# SoftCore_SA_P2_PG7.net
KiCad netlist of a schematic drawn in Altium Designer
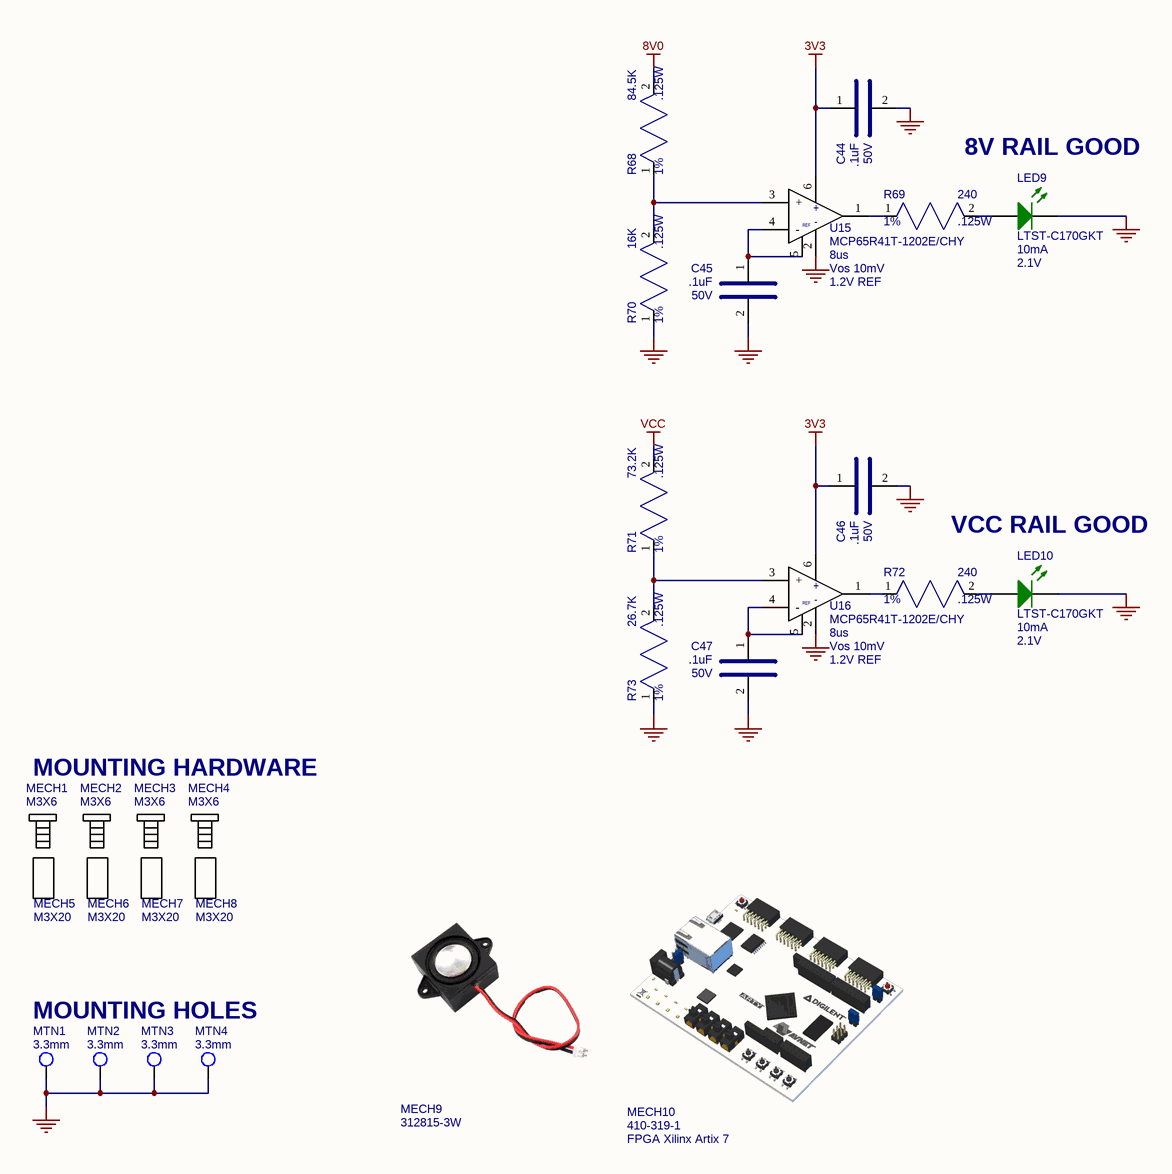
[diagram p0: SoftCore_SA_P2_PG7.SchDoc]

(export (version "E")
  (design (tool "Eeschema 10.0.6"))
  (components
    (comp (ref "C44")
      (value ".1uF")
      (footprint "CAP_0805")
      (description "CAP CER 0.1UF 50V X7R 0805")
      (fields
        (field (name "MFG") "KYOCERA AVX")
        (field (name "VOLTAGE") "50V")
        (field (name "Comment") "KGM21NR71H104KT")
      )
      (libsource (lib "IMR_LIB_SCH_R2") (part "CAP_SMD_0.1UF_50V_0805"))
    )
    (comp (ref "C45")
      (value ".1uF")
      (footprint "CAP_0805")
      (description "CAP CER 0.1UF 50V X7R 0805")
      (fields
        (field (name "MFG") "KYOCERA AVX")
        (field (name "VOLTAGE") "50V")
        (field (name "Comment") "KGM21NR71H104KT")
      )
      (libsource (lib "IMR_LIB_SCH_R2") (part "CAP_SMD_0.1UF_50V_0805"))
    )
    (comp (ref "C46")
      (value ".1uF")
      (footprint "CAP_0805")
      (description "CAP CER 0.1UF 50V X7R 0805")
      (fields
        (field (name "MFG") "KYOCERA AVX")
        (field (name "VOLTAGE") "50V")
        (field (name "Comment") "KGM21NR71H104KT")
      )
      (libsource (lib "IMR_LIB_SCH_R2") (part "CAP_SMD_0.1UF_50V_0805"))
    )
    (comp (ref "C47")
      (value ".1uF")
      (footprint "CAP_0805")
      (description "CAP CER 0.1UF 50V X7R 0805")
      (fields
        (field (name "MFG") "KYOCERA AVX")
        (field (name "VOLTAGE") "50V")
        (field (name "Comment") "KGM21NR71H104KT")
      )
      (libsource (lib "IMR_LIB_SCH_R2") (part "CAP_SMD_0.1UF_50V_0805"))
    )
    (comp (ref "LED9")
      (value "2.1V")
      (footprint "LED_0805")
      (description "LED GREEN CLEAR SMD")
      (fields
        (field (name "MFG") "Lite-On")
        (field (name "MFG_PN") "LTST-C170GKT")
        (field (name "CURRENT") "10mA")
        (field (name "Comment") "LTST-C170GKT")
      )
      (libsource (lib "IMR_LIB_SCH_R2") (part "LED_GREEN_LTST-C170GKT"))
    )
    (comp (ref "LED10")
      (value "2.1V")
      (footprint "LED_0805")
      (description "LED GREEN CLEAR SMD")
      (fields
        (field (name "MFG") "Lite-On")
        (field (name "MFG_PN") "LTST-C170GKT")
        (field (name "CURRENT") "10mA")
        (field (name "Comment") "LTST-C170GKT")
      )
      (libsource (lib "IMR_LIB_SCH_R2") (part "LED_GREEN_LTST-C170GKT"))
    )
    (comp (ref "MECH1")
      (value "RM3X6MM 2701")
      (footprint "MECHANICAL_SCREW_M3X6")
      (description "SCREW M3X6 PAN HEAD SS")
      (fields (field (name "MFG") "APM Hexseal") (field (name "SIZE") "M3X6"))
      (libsource (lib "IMR_LIB_SCH_R2") (part "MECHANICAL_SCREW_M3X6_PAN_HEAD"))
    )
    (comp (ref "MECH2")
      (value "RM3X6MM 2701")
      (footprint "MECHANICAL_SCREW_M3X6")
      (description "SCREW M3X6 PAN HEAD SS")
      (fields (field (name "MFG") "APM Hexseal") (field (name "SIZE") "M3X6"))
      (libsource (lib "IMR_LIB_SCH_R2") (part "MECHANICAL_SCREW_M3X6_PAN_HEAD"))
    )
    (comp (ref "MECH3")
      (value "RM3X6MM 2701")
      (footprint "MECHANICAL_SCREW_M3X6")
      (description "SCREW M3X6 PAN HEAD SS")
      (fields (field (name "MFG") "APM Hexseal") (field (name "SIZE") "M3X6"))
      (libsource (lib "IMR_LIB_SCH_R2") (part "MECHANICAL_SCREW_M3X6_PAN_HEAD"))
    )
    (comp (ref "MECH4")
      (value "RM3X6MM 2701")
      (footprint "MECHANICAL_SCREW_M3X6")
      (description "SCREW M3X6 PAN HEAD SS")
      (fields (field (name "MFG") "APM Hexseal") (field (name "SIZE") "M3X6"))
      (libsource (lib "IMR_LIB_SCH_R2") (part "MECHANICAL_SCREW_M3X6_PAN_HEAD"))
    )
    (comp (ref "MECH5")
      (value "24407")
      (footprint "MECHANICAL_SPACER_F_F_M3X20")
      (description "HEX STANDOFF M3 BRASS 20MM")
      (fields (field (name "MFG") "Keystone Electronics") (field (name "SIZE") "M3X20"))
      (libsource (lib "IMR_LIB_SCH_R2") (part "MECHANICAL_STANDOFF_M3X20"))
    )
    (comp (ref "MECH6")
      (value "24407")
      (footprint "MECHANICAL_SPACER_F_F_M3X20")
      (description "HEX STANDOFF M3 BRASS 20MM")
      (fields (field (name "MFG") "Keystone Electronics") (field (name "SIZE") "M3X20"))
      (libsource (lib "IMR_LIB_SCH_R2") (part "MECHANICAL_STANDOFF_M3X20"))
    )
    (comp (ref "MECH7")
      (value "24407")
      (footprint "MECHANICAL_SPACER_F_F_M3X20")
      (description "HEX STANDOFF M3 BRASS 20MM")
      (fields (field (name "MFG") "Keystone Electronics") (field (name "SIZE") "M3X20"))
      (libsource (lib "IMR_LIB_SCH_R2") (part "MECHANICAL_STANDOFF_M3X20"))
    )
    (comp (ref "MECH8")
      (value "24407")
      (footprint "MECHANICAL_SPACER_F_F_M3X20")
      (description "HEX STANDOFF M3 BRASS 20MM")
      (fields (field (name "MFG") "Keystone Electronics") (field (name "SIZE") "M3X20"))
      (libsource (lib "IMR_LIB_SCH_R2") (part "MECHANICAL_STANDOFF_M3X20"))
    )
    (comp (ref "MECH9")
      (value "312815-3W")
      (footprint "312815-3W_PCB")
      (description "SPEAKER PANEL MOUNT")
      (fields (field (name "MFG") "ARDUINO") (field (name "MFG_PN") "312815-3W"))
      (libsource (lib "IMR_LIB_SCH_R2") (part "MECHANICAL_SPEAKER_MOUNTED"))
    )
    (comp (ref "MECH10")
      (value "FPGA Xilinx Artix 7")
      (footprint "ARTY_A7_DEV_BOARD")
      (description "DEVELOPMENT BOARD FPGA XILINX A7")
      (fields
        (field (name "MFG") "Digilent, Inc.")
        (field (name "MFG_PN") "410-319-1")
        (field (name "Comment") "410-319-1")
      )
      (libsource (lib "IMR_LIB_SCH_R2") (part "MODULE_ARTY_A7"))
    )
    (comp (ref "MTN1")
      (value "~")
      (footprint "PMG_MT_HOLE_3.3MM")
      (description "MOUNTING HOLE 3.3MM")
      (fields (field (name "HOLE SIZE") "3.3mm"))
      (libsource (lib "IMR_LIB_SCH_R2") (part "MTN_HOLE_3.3MM"))
    )
    (comp (ref "MTN2")
      (value "~")
      (footprint "PMG_MT_HOLE_3.3MM")
      (description "MOUNTING HOLE 3.3MM")
      (fields (field (name "HOLE SIZE") "3.3mm"))
      (libsource (lib "IMR_LIB_SCH_R2") (part "MTN_HOLE_3.3MM"))
    )
    (comp (ref "MTN3")
      (value "~")
      (footprint "PMG_MT_HOLE_3.3MM")
      (description "MOUNTING HOLE 3.3MM")
      (fields (field (name "HOLE SIZE") "3.3mm"))
      (libsource (lib "IMR_LIB_SCH_R2") (part "MTN_HOLE_3.3MM"))
    )
    (comp (ref "MTN4")
      (value "~")
      (footprint "PMG_MT_HOLE_3.3MM")
      (description "MOUNTING HOLE 3.3MM")
      (fields (field (name "HOLE SIZE") "3.3mm"))
      (libsource (lib "IMR_LIB_SCH_R2") (part "MTN_HOLE_3.3MM"))
    )
    (comp (ref "R68")
      (value "84.5K")
      (footprint "RES_0805")
      (description "RES SMD 84.5K OHM 1% 1/8W 0805")
      (fields
        (field (name "MFG") "Yageo")
        (field (name "POWER") ".125W")
        (field (name "TOLERANCE") "1%")
        (field (name "Comment") "RC0805FR-0784K5L")
      )
      (libsource (lib "IMR_LIB_SCH_R2") (part "RES_SMD_84.5K_0805_1/8W_1%"))
    )
    (comp (ref "R69")
      (value "240")
      (footprint "RES_0805")
      (description "RES SMD 240 OHM 1% 1/8W 0805")
      (fields
        (field (name "MFG") "Yageo")
        (field (name "POWER") ".125W")
        (field (name "TOLERANCE") "1%")
        (field (name "Comment") "RC0805FR-13240RL")
      )
      (libsource (lib "IMR_LIB_SCH_R2") (part "RES_SMD_240_0805_1/8W_1%"))
    )
    (comp (ref "R70")
      (value "16K")
      (footprint "RES_0805")
      (description "RES SMD 16K OHM 1% 1/8W 0805")
      (fields
        (field (name "MFG") "Yageo")
        (field (name "POWER") ".125W")
        (field (name "TOLERANCE") "1%")
        (field (name "Comment") "RC0805FR-0716KL")
      )
      (libsource (lib "IMR_LIB_SCH_R2") (part "RES_SMD_16K_0805_1/8W_1%"))
    )
    (comp (ref "R71")
      (value "73.2K")
      (footprint "RES_0805")
      (description "RES SMD 73.2K OHM 1% 1/8W 0805")
      (fields
        (field (name "MFG") "Yageo")
        (field (name "POWER") ".125W")
        (field (name "TOLERANCE") "1%")
        (field (name "Comment") "RC0805FR-0773K2L")
      )
      (libsource (lib "IMR_LIB_SCH_R2") (part "RES_SMD_73.2K_0805_1/8W_1%"))
    )
    (comp (ref "R72")
      (value "240")
      (footprint "RES_0805")
      (description "RES SMD 240 OHM 1% 1/8W 0805")
      (fields
        (field (name "MFG") "Yageo")
        (field (name "POWER") ".125W")
        (field (name "TOLERANCE") "1%")
        (field (name "Comment") "RC0805FR-13240RL")
      )
      (libsource (lib "IMR_LIB_SCH_R2") (part "RES_SMD_240_0805_1/8W_1%"))
    )
    (comp (ref "R73")
      (value "26.7K")
      (footprint "RES_0805")
      (description "RES SMD 26.7K OHM 1% 1/8W 0805")
      (fields
        (field (name "MFG") "Yageo")
        (field (name "POWER") ".125W")
        (field (name "TOLERANCE") "1%")
        (field (name "Comment") "RC0805FR-0726K7L")
      )
      (libsource (lib "IMR_LIB_SCH_R2") (part "RES_SMD_26.7K_0805_1/8W_1%"))
    )
    (comp (ref "U15")
      (value "MCP65R41T-1202E/CHY")
      (footprint "SOT-23-6_MC_MCH")
      (description "IC COMPARATOR 1 W/VOLT REF SOT23")
      (fields
        (field (name "MFG") "Microchip Technology")
        (field (name "VOLTAGE REFERENCE") "1.2V REF")
        (field (name "MFG_PN") "MCP65R41T-1202E/CHY")
        (field (name "PROPAGATION DELAY") "8us")
        (field (name "VOS") "Vos 10mV")
      )
      (libsource (lib "IMR_LIB_SCH_R2") (part "IC_COMPARATOR_MCP65R41T-1202E/CHY"))
    )
    (comp (ref "U16")
      (value "MCP65R41T-1202E/CHY")
      (footprint "SOT-23-6_MC_MCH")
      (description "IC COMPARATOR 1 W/VOLT REF SOT23")
      (fields
        (field (name "MFG") "Microchip Technology")
        (field (name "VOLTAGE REFERENCE") "1.2V REF")
        (field (name "MFG_PN") "MCP65R41T-1202E/CHY")
        (field (name "PROPAGATION DELAY") "8us")
        (field (name "VOS") "Vos 10mV")
      )
      (libsource (lib "IMR_LIB_SCH_R2") (part "IC_COMPARATOR_MCP65R41T-1202E/CHY"))
    )
  )
  (nets
    (net (code "1") (name "3V3") (class "Default")
      (node (ref "C44") (pin "1") (pinfunction "1_1") (pintype "passive"))
      (node (ref "C46") (pin "1") (pinfunction "1_1") (pintype "passive"))
      (node (ref "U15") (pin "6") (pintype "passive"))
      (node (ref "U16") (pin "6") (pintype "passive"))
    )
    (net (code "2") (name "8V0") (class "Default")
      (node (ref "R68") (pin "2") (pinfunction "2_2") (pintype "passive"))
    )
    (net (code "3") (name "GND") (class "Default")
      (node (ref "C44") (pin "2") (pinfunction "2_2") (pintype "passive"))
      (node (ref "C45") (pin "2") (pinfunction "2_2") (pintype "passive"))
      (node (ref "C46") (pin "2") (pinfunction "2_2") (pintype "passive"))
      (node (ref "C47") (pin "2") (pinfunction "2_2") (pintype "passive"))
      (node (ref "LED10") (pin "K") (pinfunction "K_K") (pintype "passive"))
      (node (ref "LED9") (pin "K") (pinfunction "K_K") (pintype "passive"))
      (node (ref "MTN1") (pin "1") (pintype "passive"))
      (node (ref "MTN2") (pin "1") (pintype "passive"))
      (node (ref "MTN3") (pin "1") (pintype "passive"))
      (node (ref "MTN4") (pin "1") (pintype "passive"))
      (node (ref "R70") (pin "1") (pinfunction "1_1") (pintype "passive"))
      (node (ref "R73") (pin "1") (pinfunction "1_1") (pintype "passive"))
      (node (ref "U15") (pin "2") (pintype "passive"))
      (node (ref "U16") (pin "2") (pintype "passive"))
    )
    (net (code "4") (name "Net-(LED9-PadA)") (class "Default")
      (node (ref "LED9") (pin "A") (pinfunction "A_A") (pintype "passive"))
      (node (ref "R69") (pin "2") (pinfunction "2_2") (pintype "passive"))
    )
    (net (code "5") (name "Net-(LED10-PadA)") (class "Default")
      (node (ref "LED10") (pin "A") (pinfunction "A_A") (pintype "passive"))
      (node (ref "R72") (pin "2") (pinfunction "2_2") (pintype "passive"))
    )
    (net (code "6") (name "Net-(R69-Pad1)") (class "Default")
      (node (ref "R69") (pin "1") (pinfunction "1_1") (pintype "passive"))
      (node (ref "U15") (pin "1") (pintype "passive"))
    )
    (net (code "7") (name "Net-(R72-Pad1)") (class "Default")
      (node (ref "R72") (pin "1") (pinfunction "1_1") (pintype "passive"))
      (node (ref "U16") (pin "1") (pintype "passive"))
    )
    (net (code "8") (name "Net-(U15-+)") (class "Default")
      (node (ref "R68") (pin "1") (pinfunction "1_1") (pintype "passive"))
      (node (ref "R70") (pin "2") (pinfunction "2_2") (pintype "passive"))
      (node (ref "U15") (pin "3") (pinfunction "+_3") (pintype "passive"))
    )
    (net (code "9") (name "Net-(U15--)") (class "Default")
      (node (ref "C45") (pin "1") (pinfunction "1_1") (pintype "passive"))
      (node (ref "U15") (pin "4") (pinfunction "-_4") (pintype "passive"))
      (node (ref "U15") (pin "5") (pintype "passive"))
    )
    (net (code "10") (name "Net-(U16-+)") (class "Default")
      (node (ref "R71") (pin "1") (pinfunction "1_1") (pintype "passive"))
      (node (ref "R73") (pin "2") (pinfunction "2_2") (pintype "passive"))
      (node (ref "U16") (pin "3") (pinfunction "+_3") (pintype "passive"))
    )
    (net (code "11") (name "Net-(U16--)") (class "Default")
      (node (ref "C47") (pin "1") (pinfunction "1_1") (pintype "passive"))
      (node (ref "U16") (pin "4") (pinfunction "-_4") (pintype "passive"))
      (node (ref "U16") (pin "5") (pintype "passive"))
    )
    (net (code "12") (name "VCC") (class "Default")
      (node (ref "R71") (pin "2") (pinfunction "2_2") (pintype "passive"))
    )
  )
)
